# Power_Connections.net
KiCad netlist of a schematic drawn in Altium Designer
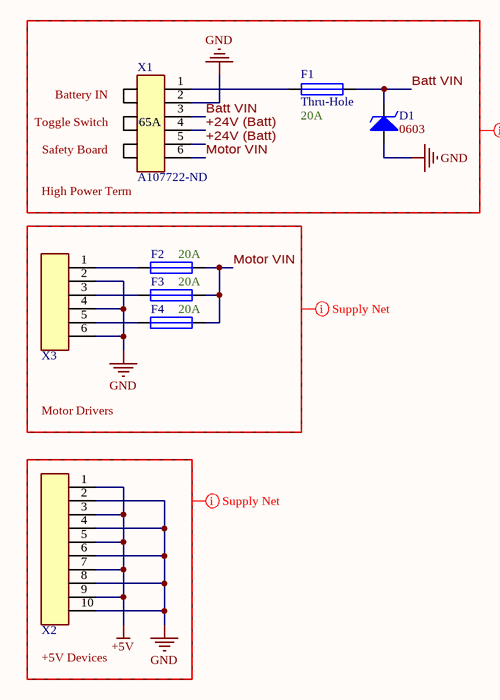
[diagram p0: Power Connections.SchDoc]

(export (version "E")
  (design (tool "Eeschema 10.0.6"))
  (components
    (comp (ref "D1")
      (value "TVS/Zener")
      (footprint "[Diode] SMD 0603")
      (description "Generic")
      (fields (field (name "SIZE PACKAGE") "0603"))
      (libsource (lib "RADM Components") (part "[Diode] TVS Diode"))
    )
    (comp (ref "F1")
      (value "Thru-Hole")
      (footprint "[Fuse] Thru-Hole Blade")
      (fields (field (name "CAPACITY") "20A"))
      (libsource (lib "RADM Components") (part "[Fuse] Thru-Hole Blade"))
    )
    (comp (ref "F2")
      (value "Thru-Hole")
      (footprint "[Fuse] Thru-Hole Blade")
      (fields (field (name "CAPACITY") "20A"))
      (libsource (lib "RADM Components") (part "[Fuse] Thru-Hole Blade"))
    )
    (comp (ref "F3")
      (value "Thru-Hole")
      (footprint "[Fuse] Thru-Hole Blade")
      (fields (field (name "CAPACITY") "20A"))
      (libsource (lib "RADM Components") (part "[Fuse] Thru-Hole Blade"))
    )
    (comp (ref "F4")
      (value "Thru-Hole")
      (footprint "[Fuse] Thru-Hole Blade")
      (fields (field (name "CAPACITY") "20A"))
      (libsource (lib "RADM Components") (part "[Fuse] Thru-Hole Blade"))
    )
    (comp (ref "X1")
      (value "[Screw Terminal] 6pin 65A")
      (footprint "[Screw Terminal] 6pin 65A")
      (description "Remember to order 3 of the screw term for one of these!")
      (fields (field (name "SUPPLIER PART NUMBER 1") "A107722-ND"))
      (libsource (lib "RADM Connectors") (part "[Screw Terminal] 6pin 65A"))
    )
    (comp (ref "X2")
      (value "[Screw Terminal] 10pin")
      (footprint "[Screw Terminal] 10pin")
      (description "x5")
      (libsource (lib "RADM Connectors") (part "[Screw Terminal] 10pin"))
    )
    (comp (ref "X3")
      (value "[Screw Terminal] 6pin")
      (footprint "[Screw Terminal] 6pin")
      (description "x3")
      (libsource (lib "RADM Connectors") (part "[Screw Terminal] 6pin"))
    )
  )
  (nets
    (net (code "1") (name "+5V") (class "Default")
      (node (ref "X2") (pin "1") (pintype "power_in"))
      (node (ref "X2") (pin "3") (pintype "power_in"))
      (node (ref "X2") (pin "5") (pintype "power_in"))
      (node (ref "X2") (pin "7") (pintype "power_in"))
      (node (ref "X2") (pin "9") (pintype "power_in"))
    )
    (net (code "2") (name "/+24V (Batt)") (class "Default")
      (node (ref "X1") (pin "4") (pintype "passive"))
      (node (ref "X1") (pin "5") (pinfunction "5_5") (pintype "power_in"))
    )
    (net (code "3") (name "/Batt VIN") (class "Default")
      (node (ref "D1") (pin "1") (pinfunction "Cathode_1") (pintype "passive"))
      (node (ref "F1") (pin "2") (pinfunction "2_2") (pintype "passive"))
      (node (ref "X1") (pin "3") (pintype "passive"))
    )
    (net (code "4") (name "/Motor VIN") (class "Default")
      (node (ref "F2") (pin "2") (pinfunction "2_2") (pintype "passive"))
      (node (ref "F3") (pin "2") (pinfunction "2_2") (pintype "passive"))
      (node (ref "F4") (pin "2") (pinfunction "2_2") (pintype "passive"))
      (node (ref "X1") (pin "6") (pinfunction "6_6") (pintype "power_in"))
    )
    (net (code "5") (name "GND") (class "Default")
      (node (ref "D1") (pin "2") (pinfunction "Anode_2") (pintype "passive"))
      (node (ref "X1") (pin "2") (pintype "passive"))
      (node (ref "X2") (pin "10") (pintype "power_in"))
      (node (ref "X2") (pin "2") (pintype "power_in"))
      (node (ref "X2") (pin "4") (pintype "power_in"))
      (node (ref "X2") (pin "6") (pintype "power_in"))
      (node (ref "X2") (pin "8") (pintype "power_in"))
      (node (ref "X3") (pin "2") (pintype "power_in"))
      (node (ref "X3") (pin "4") (pintype "power_in"))
      (node (ref "X3") (pin "6") (pintype "power_in"))
    )
    (net (code "6") (name "Net-(F1-Pad1)") (class "Default")
      (node (ref "F1") (pin "1") (pinfunction "1_1") (pintype "passive"))
      (node (ref "X1") (pin "1") (pintype "passive"))
    )
    (net (code "7") (name "Net-(F2-Pad1)") (class "Default")
      (node (ref "F2") (pin "1") (pinfunction "1_1") (pintype "passive"))
      (node (ref "X3") (pin "1") (pintype "power_in"))
    )
    (net (code "8") (name "Net-(F3-Pad1)") (class "Default")
      (node (ref "F3") (pin "1") (pinfunction "1_1") (pintype "passive"))
      (node (ref "X3") (pin "3") (pintype "power_in"))
    )
    (net (code "9") (name "Net-(F4-Pad1)") (class "Default")
      (node (ref "F4") (pin "1") (pinfunction "1_1") (pintype "passive"))
      (node (ref "X3") (pin "5") (pintype "power_in"))
    )
  )
)
